# SCB_PLLs.net
KiCad netlist of a schematic drawn in Altium Designer
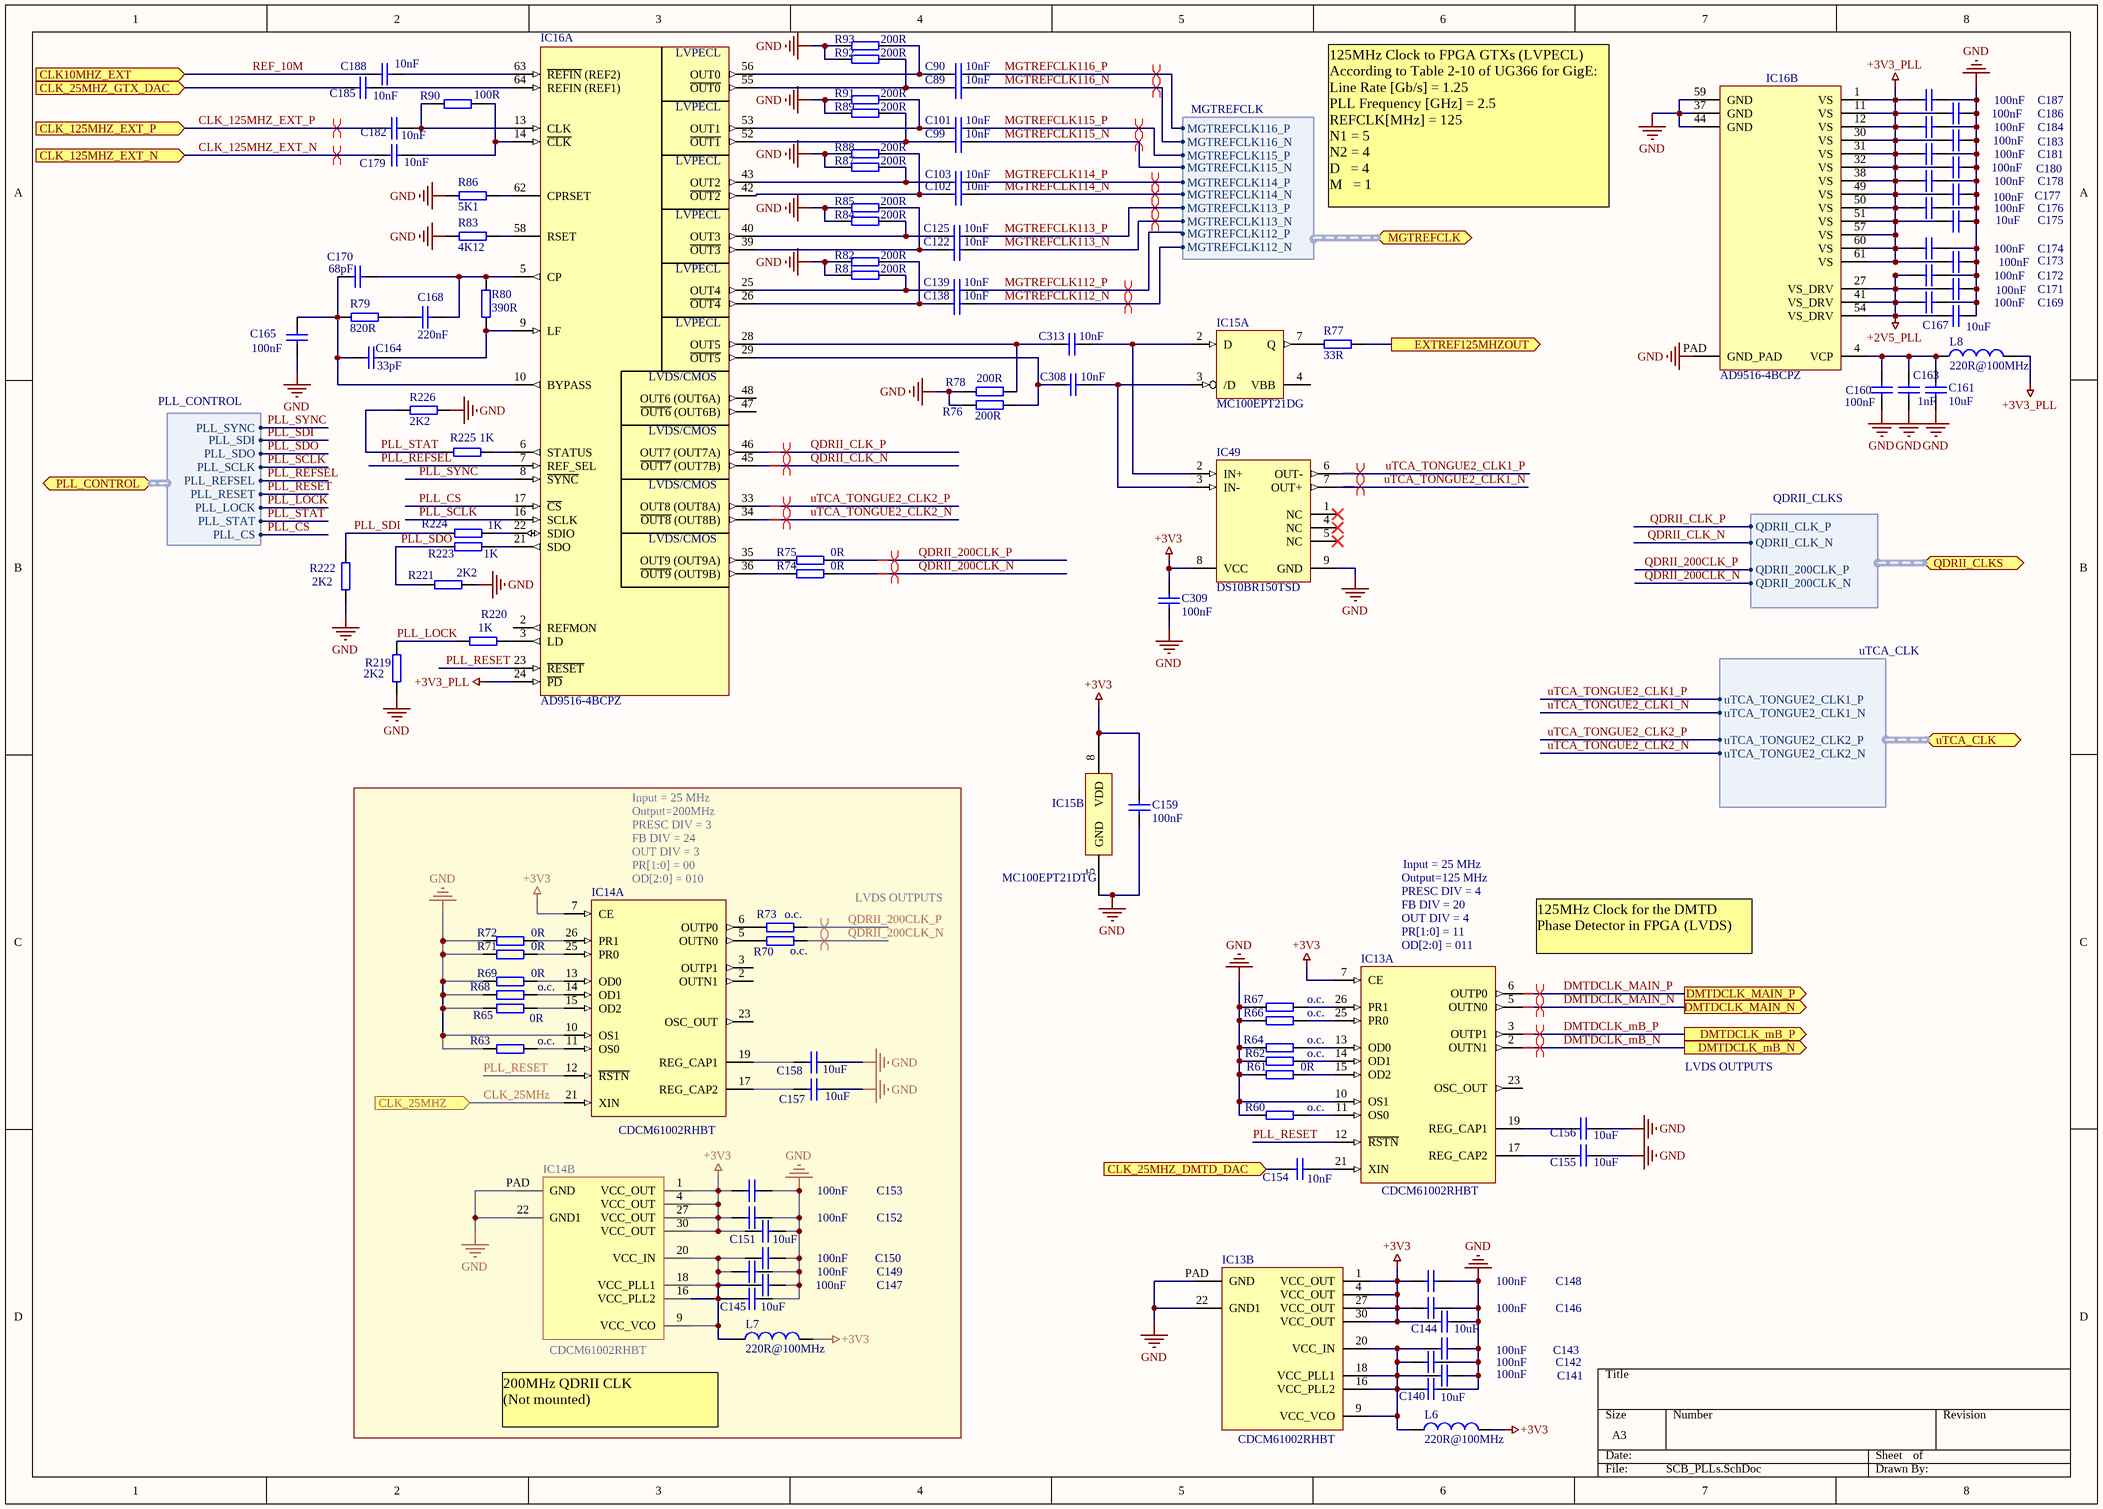
[diagram p0: SCB_PLLs.SchDoc]

(export (version "E")
  (design (tool "Eeschema 10.0.6"))
  (components
    (comp (ref "C89")
      (value "10nF")
      (footprint "CC1005-0402")
      (description "Capacitor")
      (fields
        (field (name "TOLERANCE") "±10%")
        (field (name "VOLTAGE") "25V")
        (field (name "PUBLISHER") "Altium Limited")
      )
      (libsource (lib "wr_switch") (part "Cap"))
    )
    (comp (ref "C90")
      (value "10nF")
      (footprint "CC1005-0402")
      (description "Capacitor")
      (fields
        (field (name "TOLERANCE") "±10%")
        (field (name "VOLTAGE") "25V")
        (field (name "PUBLISHER") "Altium Limited")
      )
      (libsource (lib "wr_switch") (part "Cap"))
    )
    (comp (ref "C99")
      (value "10nF")
      (footprint "CC1005-0402")
      (description "Capacitor")
      (fields
        (field (name "TOLERANCE") "±10%")
        (field (name "VOLTAGE") "25V")
        (field (name "PUBLISHER") "Altium Limited")
      )
      (libsource (lib "wr_switch") (part "Cap"))
    )
    (comp (ref "C101")
      (value "10nF")
      (footprint "CC1005-0402")
      (description "Capacitor")
      (fields
        (field (name "TOLERANCE") "±10%")
        (field (name "VOLTAGE") "25V")
        (field (name "PUBLISHER") "Altium Limited")
      )
      (libsource (lib "wr_switch") (part "Cap"))
    )
    (comp (ref "C102")
      (value "10nF")
      (footprint "CC1005-0402")
      (description "Capacitor")
      (fields
        (field (name "TOLERANCE") "±10%")
        (field (name "VOLTAGE") "25V")
        (field (name "PUBLISHER") "Altium Limited")
      )
      (libsource (lib "wr_switch") (part "Cap"))
    )
    (comp (ref "C103")
      (value "10nF")
      (footprint "CC1005-0402")
      (description "Capacitor")
      (fields
        (field (name "TOLERANCE") "±10%")
        (field (name "VOLTAGE") "25V")
        (field (name "PUBLISHER") "Altium Limited")
      )
      (libsource (lib "wr_switch") (part "Cap"))
    )
    (comp (ref "C122")
      (value "10nF")
      (footprint "CC1005-0402")
      (description "Capacitor")
      (fields
        (field (name "TOLERANCE") "±10%")
        (field (name "VOLTAGE") "25V")
        (field (name "PUBLISHER") "Altium Limited")
      )
      (libsource (lib "wr_switch") (part "Cap"))
    )
    (comp (ref "C125")
      (value "10nF")
      (footprint "CC1005-0402")
      (description "Capacitor")
      (fields
        (field (name "TOLERANCE") "±10%")
        (field (name "VOLTAGE") "25V")
        (field (name "PUBLISHER") "Altium Limited")
      )
      (libsource (lib "wr_switch") (part "Cap"))
    )
    (comp (ref "C138")
      (value "10nF")
      (footprint "CC1005-0402")
      (description "Capacitor")
      (fields
        (field (name "TOLERANCE") "±10%")
        (field (name "VOLTAGE") "25V")
        (field (name "PUBLISHER") "Altium Limited")
      )
      (libsource (lib "wr_switch") (part "Cap"))
    )
    (comp (ref "C139")
      (value "10nF")
      (footprint "CC1005-0402")
      (description "Capacitor")
      (fields
        (field (name "TOLERANCE") "±10%")
        (field (name "VOLTAGE") "25V")
        (field (name "PUBLISHER") "Altium Limited")
      )
      (libsource (lib "wr_switch") (part "Cap"))
    )
    (comp (ref "C140")
      (value "10uF")
      (footprint "CC1608-0603")
      (description "Capacitor")
      (fields
        (field (name "TOLERANCE") "±20%")
        (field (name "VOLTAGE") "6.3V")
        (field (name "PUBLISHER") "Altium Limited")
      )
      (libsource (lib "wr_switch") (part "Cap"))
    )
    (comp (ref "C141")
      (value "100nF")
      (footprint "CC1005-0402")
      (description "Capacitor")
      (fields
        (field (name "TOLERANCE") "±10%")
        (field (name "VOLTAGE") "16V")
        (field (name "PUBLISHER") "Altium Limited")
      )
      (libsource (lib "wr_switch") (part "Cap"))
    )
    (comp (ref "C142")
      (value "100nF")
      (footprint "CC1005-0402")
      (description "Capacitor")
      (fields
        (field (name "TOLERANCE") "±10%")
        (field (name "VOLTAGE") "16V")
        (field (name "PUBLISHER") "Altium Limited")
      )
      (libsource (lib "wr_switch") (part "Cap"))
    )
    (comp (ref "C143")
      (value "100nF")
      (footprint "CC1005-0402")
      (description "Capacitor")
      (fields
        (field (name "TOLERANCE") "±10%")
        (field (name "VOLTAGE") "16V")
        (field (name "PUBLISHER") "Altium Limited")
      )
      (libsource (lib "wr_switch") (part "Cap"))
    )
    (comp (ref "C144")
      (value "10uF")
      (footprint "CC1608-0603")
      (description "Capacitor")
      (fields
        (field (name "TOLERANCE") "±20%")
        (field (name "VOLTAGE") "6.3V")
        (field (name "PUBLISHER") "Altium Limited")
      )
      (libsource (lib "wr_switch") (part "Cap"))
    )
    (comp (ref "C145")
      (value "10uF")
      (footprint "CC1608-0603")
      (description "Capacitor")
      (fields
        (field (name "TOLERANCE") "±20%")
        (field (name "VOLTAGE") "6.3V")
        (field (name "PUBLISHER") "Altium Limited")
      )
      (libsource (lib "wr_switch") (part "Cap"))
    )
    (comp (ref "C146")
      (value "100nF")
      (footprint "CC1005-0402")
      (description "Capacitor")
      (fields
        (field (name "TOLERANCE") "±10%")
        (field (name "VOLTAGE") "16V")
        (field (name "PUBLISHER") "Altium Limited")
      )
      (libsource (lib "wr_switch") (part "Cap"))
    )
    (comp (ref "C147")
      (value "100nF")
      (footprint "CC1005-0402")
      (description "Capacitor")
      (fields
        (field (name "TOLERANCE") "±10%")
        (field (name "VOLTAGE") "16V")
        (field (name "PUBLISHER") "Altium Limited")
      )
      (libsource (lib "wr_switch") (part "Cap"))
    )
    (comp (ref "C148")
      (value "100nF")
      (footprint "CC1005-0402")
      (description "Capacitor")
      (fields
        (field (name "TOLERANCE") "±10%")
        (field (name "VOLTAGE") "16V")
        (field (name "PUBLISHER") "Altium Limited")
      )
      (libsource (lib "wr_switch") (part "Cap"))
    )
    (comp (ref "C149")
      (value "100nF")
      (footprint "CC1005-0402")
      (description "Capacitor")
      (fields
        (field (name "TOLERANCE") "±10%")
        (field (name "VOLTAGE") "16V")
        (field (name "PUBLISHER") "Altium Limited")
      )
      (libsource (lib "wr_switch") (part "Cap"))
    )
    (comp (ref "C150")
      (value "100nF")
      (footprint "CC1005-0402")
      (description "Capacitor")
      (fields
        (field (name "TOLERANCE") "±10%")
        (field (name "VOLTAGE") "16V")
        (field (name "PUBLISHER") "Altium Limited")
      )
      (libsource (lib "wr_switch") (part "Cap"))
    )
    (comp (ref "C151")
      (value "10uF")
      (footprint "CC1608-0603")
      (description "Capacitor")
      (fields
        (field (name "TOLERANCE") "±20%")
        (field (name "VOLTAGE") "6.3V")
        (field (name "PUBLISHER") "Altium Limited")
      )
      (libsource (lib "wr_switch") (part "Cap"))
    )
    (comp (ref "C152")
      (value "100nF")
      (footprint "CC1005-0402")
      (description "Capacitor")
      (fields
        (field (name "TOLERANCE") "±10%")
        (field (name "VOLTAGE") "16V")
        (field (name "PUBLISHER") "Altium Limited")
      )
      (libsource (lib "wr_switch") (part "Cap"))
    )
    (comp (ref "C153")
      (value "100nF")
      (footprint "CC1005-0402")
      (description "Capacitor")
      (fields
        (field (name "TOLERANCE") "±10%")
        (field (name "VOLTAGE") "16V")
        (field (name "PUBLISHER") "Altium Limited")
      )
      (libsource (lib "wr_switch") (part "Cap"))
    )
    (comp (ref "C154")
      (value "10nF")
      (footprint "CC1005-0402")
      (description "Capacitor")
      (fields
        (field (name "TOLERANCE") "±10%")
        (field (name "VOLTAGE") "25V")
        (field (name "PUBLISHER") "Altium Limited")
      )
      (libsource (lib "wr_switch") (part "Cap"))
    )
    (comp (ref "C155")
      (value "10uF")
      (footprint "CC1608-0603")
      (description "Capacitor")
      (fields
        (field (name "TOLERANCE") "±20%")
        (field (name "VOLTAGE") "6.3V")
        (field (name "PUBLISHER") "Altium Limited")
      )
      (libsource (lib "wr_switch") (part "Cap"))
    )
    (comp (ref "C156")
      (value "10uF")
      (footprint "CC1608-0603")
      (description "Capacitor")
      (fields
        (field (name "TOLERANCE") "±20%")
        (field (name "VOLTAGE") "6.3V")
        (field (name "PUBLISHER") "Altium Limited")
      )
      (libsource (lib "wr_switch") (part "Cap"))
    )
    (comp (ref "C157")
      (value "10uF")
      (footprint "CC1608-0603")
      (description "Capacitor")
      (fields
        (field (name "TOLERANCE") "±20%")
        (field (name "VOLTAGE") "6.3V")
        (field (name "PUBLISHER") "Altium Limited")
      )
      (libsource (lib "wr_switch") (part "Cap"))
    )
    (comp (ref "C158")
      (value "10uF")
      (footprint "CC1608-0603")
      (description "Capacitor")
      (fields
        (field (name "TOLERANCE") "±20%")
        (field (name "VOLTAGE") "6.3V")
        (field (name "PUBLISHER") "Altium Limited")
      )
      (libsource (lib "wr_switch") (part "Cap"))
    )
    (comp (ref "C159")
      (value "100nF")
      (footprint "CC1005-0402")
      (description "Capacitor")
      (fields
        (field (name "TOLERANCE") "±10%")
        (field (name "VOLTAGE") "16V")
        (field (name "PUBLISHER") "Altium Limited")
      )
      (libsource (lib "wr_switch") (part "Cap"))
    )
    (comp (ref "C160")
      (value "100nF")
      (footprint "CC1005-0402")
      (description "Capacitor")
      (fields
        (field (name "TOLERANCE") "±10%")
        (field (name "VOLTAGE") "16V")
        (field (name "PUBLISHER") "Altium Limited")
      )
      (libsource (lib "wr_switch") (part "Cap"))
    )
    (comp (ref "C161")
      (value "10uF")
      (footprint "CC1608-0603")
      (description "Capacitor")
      (fields
        (field (name "TOLERANCE") "±20%")
        (field (name "VOLTAGE") "6.3V")
        (field (name "PUBLISHER") "Altium Limited")
      )
      (libsource (lib "wr_switch") (part "Cap"))
    )
    (comp (ref "C163")
      (value "1nF")
      (footprint "CC1005-0402")
      (description "Capacitor")
      (fields
        (field (name "TOLERANCE") "±10%")
        (field (name "VOLTAGE") "25V")
        (field (name "PUBLISHER") "Altium Limited")
      )
      (libsource (lib "wr_switch") (part "Cap"))
    )
    (comp (ref "C164")
      (value "33pF")
      (footprint "CC1608-0603")
      (description "Capacitor")
      (fields
        (field (name "TOLERANCE") "±5%")
        (field (name "VOLTAGE") "50V")
        (field (name "PUBLISHER") "Altium Limited")
      )
      (libsource (lib "wr_switch") (part "Cap"))
    )
    (comp (ref "C165")
      (value "100nF")
      (footprint "CC1608-0603")
      (description "Capacitor")
      (fields
        (field (name "TOLERANCE") "±10%")
        (field (name "VOLTAGE") "50V")
        (field (name "PUBLISHER") "Altium Limited")
      )
      (libsource (lib "wr_switch") (part "Cap"))
    )
    (comp (ref "C167")
      (value "10uF")
      (footprint "CC1608-0603")
      (description "Capacitor")
      (fields
        (field (name "TOLERANCE") "±20%")
        (field (name "VOLTAGE") "6.3V")
        (field (name "PUBLISHER") "Altium Limited")
      )
      (libsource (lib "wr_switch") (part "Cap"))
    )
    (comp (ref "C168")
      (value "220nF")
      (footprint "CC1608-0603")
      (description "Capacitor")
      (fields
        (field (name "TOLERANCE") "±10%")
        (field (name "VOLTAGE") "10V")
        (field (name "PUBLISHER") "Altium Limited")
      )
      (libsource (lib "wr_switch") (part "Cap"))
    )
    (comp (ref "C169")
      (value "100nF")
      (footprint "CC1005-0402")
      (description "Capacitor")
      (fields
        (field (name "TOLERANCE") "±10%")
        (field (name "VOLTAGE") "16V")
        (field (name "PUBLISHER") "Altium Limited")
      )
      (libsource (lib "wr_switch") (part "Cap"))
    )
    (comp (ref "C170")
      (value "68pF")
      (footprint "CC1608-0603")
      (description "Capacitor")
      (fields
        (field (name "TOLERANCE") "±5%")
        (field (name "VOLTAGE") "50V")
        (field (name "PUBLISHER") "Altium Limited")
      )
      (libsource (lib "wr_switch") (part "Cap"))
    )
    (comp (ref "C171")
      (value "100nF")
      (footprint "CC1005-0402")
      (description "Capacitor")
      (fields
        (field (name "TOLERANCE") "±10%")
        (field (name "VOLTAGE") "16V")
        (field (name "PUBLISHER") "Altium Limited")
      )
      (libsource (lib "wr_switch") (part "Cap"))
    )
    (comp (ref "C172")
      (value "100nF")
      (footprint "CC1005-0402")
      (description "Capacitor")
      (fields
        (field (name "TOLERANCE") "±10%")
        (field (name "VOLTAGE") "16V")
        (field (name "PUBLISHER") "Altium Limited")
      )
      (libsource (lib "wr_switch") (part "Cap"))
    )
    (comp (ref "C173")
      (value "100nF")
      (footprint "CC1005-0402")
      (description "Capacitor")
      (fields
        (field (name "TOLERANCE") "±10%")
        (field (name "VOLTAGE") "16V")
        (field (name "PUBLISHER") "Altium Limited")
      )
      (libsource (lib "wr_switch") (part "Cap"))
    )
    (comp (ref "C174")
      (value "100nF")
      (footprint "CC1005-0402")
      (description "Capacitor")
      (fields
        (field (name "TOLERANCE") "±10%")
        (field (name "VOLTAGE") "16V")
        (field (name "PUBLISHER") "Altium Limited")
      )
      (libsource (lib "wr_switch") (part "Cap"))
    )
    (comp (ref "C175")
      (value "10uF")
      (footprint "CC1608-0603")
      (description "Capacitor")
      (fields
        (field (name "TOLERANCE") "±20%")
        (field (name "VOLTAGE") "6.3V")
        (field (name "PUBLISHER") "Altium Limited")
      )
      (libsource (lib "wr_switch") (part "Cap"))
    )
    (comp (ref "C176")
      (value "100nF")
      (footprint "CC1005-0402")
      (description "Capacitor")
      (fields
        (field (name "TOLERANCE") "±10%")
        (field (name "VOLTAGE") "16V")
        (field (name "PUBLISHER") "Altium Limited")
      )
      (libsource (lib "wr_switch") (part "Cap"))
    )
    (comp (ref "C177")
      (value "100nF")
      (footprint "CC1005-0402")
      (description "Capacitor")
      (fields
        (field (name "TOLERANCE") "±10%")
        (field (name "VOLTAGE") "16V")
        (field (name "PUBLISHER") "Altium Limited")
      )
      (libsource (lib "wr_switch") (part "Cap"))
    )
    (comp (ref "C178")
      (value "100nF")
      (footprint "CC1005-0402")
      (description "Capacitor")
      (fields
        (field (name "TOLERANCE") "±10%")
        (field (name "VOLTAGE") "16V")
        (field (name "PUBLISHER") "Altium Limited")
      )
      (libsource (lib "wr_switch") (part "Cap"))
    )
    (comp (ref "C179")
      (value "10nF")
      (footprint "CC1005-0402")
      (description "Capacitor")
      (fields
        (field (name "TOLERANCE") "±10%")
        (field (name "VOLTAGE") "25V")
        (field (name "PUBLISHER") "Altium Limited")
      )
      (libsource (lib "wr_switch") (part "Cap"))
    )
    (comp (ref "C180")
      (value "100nF")
      (footprint "CC1005-0402")
      (description "Capacitor")
      (fields
        (field (name "TOLERANCE") "±10%")
        (field (name "VOLTAGE") "16V")
        (field (name "PUBLISHER") "Altium Limited")
      )
      (libsource (lib "wr_switch") (part "Cap"))
    )
    (comp (ref "C181")
      (value "100nF")
      (footprint "CC1005-0402")
      (description "Capacitor")
      (fields
        (field (name "TOLERANCE") "±10%")
        (field (name "VOLTAGE") "16V")
        (field (name "PUBLISHER") "Altium Limited")
      )
      (libsource (lib "wr_switch") (part "Cap"))
    )
    (comp (ref "C182")
      (value "10nF")
      (footprint "CC1005-0402")
      (description "Capacitor")
      (fields
        (field (name "TOLERANCE") "±10%")
        (field (name "VOLTAGE") "25V")
        (field (name "PUBLISHER") "Altium Limited")
      )
      (libsource (lib "wr_switch") (part "Cap"))
    )
    (comp (ref "C183")
      (value "100nF")
      (footprint "CC1005-0402")
      (description "Capacitor")
      (fields
        (field (name "TOLERANCE") "±10%")
        (field (name "VOLTAGE") "16V")
        (field (name "PUBLISHER") "Altium Limited")
      )
      (libsource (lib "wr_switch") (part "Cap"))
    )
    (comp (ref "C184")
      (value "100nF")
      (footprint "CC1005-0402")
      (description "Capacitor")
      (fields
        (field (name "TOLERANCE") "±10%")
        (field (name "VOLTAGE") "16V")
        (field (name "PUBLISHER") "Altium Limited")
      )
      (libsource (lib "wr_switch") (part "Cap"))
    )
    (comp (ref "C185")
      (value "10nF")
      (footprint "CC1005-0402")
      (description "Capacitor")
      (fields
        (field (name "TOLERANCE") "±10%")
        (field (name "VOLTAGE") "25V")
        (field (name "PUBLISHER") "Altium Limited")
      )
      (libsource (lib "wr_switch") (part "Cap"))
    )
    (comp (ref "C186")
      (value "100nF")
      (footprint "CC1005-0402")
      (description "Capacitor")
      (fields
        (field (name "TOLERANCE") "±10%")
        (field (name "VOLTAGE") "16V")
        (field (name "PUBLISHER") "Altium Limited")
      )
      (libsource (lib "wr_switch") (part "Cap"))
    )
    (comp (ref "C187")
      (value "100nF")
      (footprint "CC1005-0402")
      (description "Capacitor")
      (fields
        (field (name "TOLERANCE") "±10%")
        (field (name "VOLTAGE") "16V")
        (field (name "PUBLISHER") "Altium Limited")
      )
      (libsource (lib "wr_switch") (part "Cap"))
    )
    (comp (ref "C188")
      (value "10nF")
      (footprint "CC1005-0402")
      (description "Capacitor")
      (fields
        (field (name "TOLERANCE") "±10%")
        (field (name "VOLTAGE") "25V")
        (field (name "PUBLISHER") "Altium Limited")
      )
      (libsource (lib "wr_switch") (part "Cap"))
    )
    (comp (ref "C308")
      (value "10nF")
      (footprint "CC1005-0402")
      (description "Capacitor")
      (fields
        (field (name "TOLERANCE") "±10%")
        (field (name "VOLTAGE") "25V")
        (field (name "PUBLISHER") "Altium Limited")
      )
      (libsource (lib "wr_switch") (part "Cap"))
    )
    (comp (ref "C309")
      (value "100nF")
      (footprint "CC1005-0402")
      (description "Capacitor")
      (fields
        (field (name "TOLERANCE") "±10%")
        (field (name "VOLTAGE") "16V")
        (field (name "PUBLISHER") "Altium Limited")
      )
      (libsource (lib "wr_switch") (part "Cap"))
    )
    (comp (ref "C313")
      (value "10nF")
      (footprint "CC1005-0402")
      (description "Capacitor")
      (fields
        (field (name "TOLERANCE") "±10%")
        (field (name "VOLTAGE") "25V")
        (field (name "PUBLISHER") "Altium Limited")
      )
      (libsource (lib "wr_switch") (part "Cap"))
    )
    (comp (ref "IC13")
      (value "CDCM61002RHBT")
      (footprint "QFN32_POWERPAD")
      (description "Low Jitter Clock Generator, Two Outpust, Integrated VCO")
      (fields (field (name "MANUFACTURER") "Texas Instruments"))
      (libsource (lib "wr_switch") (part "CDCM61002"))
    )
    (comp (ref "IC14")
      (value "CDCM61002RHBT")
      (footprint "QFN32_POWERPAD")
      (description "Low Jitter Clock Generator, Two Outpust, Integrated VCO")
      (fields (field (name "MANUFACTURER") "Texas Instruments"))
      (libsource (lib "wr_switch") (part "CDCM61002"))
    )
    (comp (ref "IC15")
      (value "MC100EPT21DG")
      (footprint "SOIC127P600-8AL")
      (description "ONSemi LVDS/LVPECL -> LVTTL/LVCMOS buffer")
      (libsource (lib "wr_switch") (part "MC100EPT21"))
    )
    (comp (ref "IC16")
      (value "AD9516-4BCPZ")
      (footprint "QFN50P900X900X100-64M")
      (description "PLL with clock fanout")
      (libsource (lib "wr_switch") (part "AD9516"))
    )
    (comp (ref "IC49")
      (value "DS10BR150TSD")
      (footprint "SDA08A")
      (description "1.0 Gbps LVDS Buffer/Repeater")
      (fields
        (field (name "MANUFACTURER") "National Semiconductor")
        (field (name "DIGIKEYPARTNUMBER") "DS10BR150TSDTR-ND")
        (field (name "PUBLISHER") "Altium Limited")
      )
      (libsource (lib "NSC Interface") (part "DS10BR150TSD"))
    )
    (comp (ref "L6")
      (value "220R@100MHz Ferrite Bead")
      (footprint "0603")
      (description "ferrite bead")
      (fields (field (name "IMPEDANCE") "220R@100MHz"))
      (libsource (lib "wr_switch") (part "L_FERRITE_BEAD"))
    )
    (comp (ref "L7")
      (value "220R@100MHz Ferrite Bead")
      (footprint "0603")
      (description "ferrite bead")
      (fields (field (name "IMPEDANCE") "220R@100MHz"))
      (libsource (lib "wr_switch") (part "L_FERRITE_BEAD"))
    )
    (comp (ref "L8")
      (value "220R@100MHz Ferrite Bead")
      (footprint "0603")
      (description "ferrite bead")
      (fields (field (name "IMPEDANCE") "220R@100MHz"))
      (libsource (lib "wr_switch") (part "L_FERRITE_BEAD"))
    )
    (comp (ref "R60")
      (value "o.c.")
      (footprint "0402")
      (description "SMD Resistor")
      (libsource (lib "wr_switch") (part "RES_SMD"))
    )
    (comp (ref "R61")
      (value "0R")
      (footprint "0402")
      (description "SMD Resistor")
      (fields (field (name "TOLERANCE") "Jumper"))
      (libsource (lib "wr_switch") (part "RES_SMD"))
    )
    (comp (ref "R62")
      (value "o.c.")
      (footprint "0402")
      (description "SMD Resistor")
      (libsource (lib "wr_switch") (part "RES_SMD"))
    )
    (comp (ref "R63")
      (value "o.c.")
      (footprint "0402")
      (description "SMD Resistor")
      (libsource (lib "wr_switch") (part "RES_SMD"))
    )
    (comp (ref "R64")
      (value "o.c.")
      (footprint "0402")
      (description "SMD Resistor")
      (libsource (lib "wr_switch") (part "RES_SMD"))
    )
    (comp (ref "R65")
      (value "0R")
      (footprint "0402")
      (description "SMD Resistor")
      (fields (field (name "TOLERANCE") "Jumper"))
      (libsource (lib "wr_switch") (part "RES_SMD"))
    )
    (comp (ref "R66")
      (value "o.c.")
      (footprint "0402")
      (description "SMD Resistor")
      (libsource (lib "wr_switch") (part "RES_SMD"))
    )
    (comp (ref "R67")
      (value "o.c.")
      (footprint "0402")
      (description "SMD Resistor")
      (libsource (lib "wr_switch") (part "RES_SMD"))
    )
    (comp (ref "R68")
      (value "o.c.")
      (footprint "0402")
      (description "SMD Resistor")
      (libsource (lib "wr_switch") (part "RES_SMD"))
    )
    (comp (ref "R69")
      (value "0R")
      (footprint "0402")
      (description "SMD Resistor")
      (fields (field (name "TOLERANCE") "Jumper"))
      (libsource (lib "wr_switch") (part "RES_SMD"))
    )
    (comp (ref "R70")
      (value "o.c.")
      (footprint "0402")
      (description "SMD Resistor")
      (libsource (lib "wr_switch") (part "RES_SMD"))
    )
    (comp (ref "R71")
      (value "0R")
      (footprint "0402")
      (description "SMD Resistor")
      (fields (field (name "TOLERANCE") "Jumper"))
      (libsource (lib "wr_switch") (part "RES_SMD"))
    )
    (comp (ref "R72")
      (value "0R")
      (footprint "0402")
      (description "SMD Resistor")
      (fields (field (name "TOLERANCE") "Jumper"))
      (libsource (lib "wr_switch") (part "RES_SMD"))
    )
    (comp (ref "R73")
      (value "o.c.")
      (footprint "0402")
      (description "SMD Resistor")
      (libsource (lib "wr_switch") (part "RES_SMD"))
    )
    (comp (ref "R74")
      (value "0R")
      (footprint "0402")
      (description "SMD Resistor")
      (fields (field (name "TOLERANCE") "Jumper"))
      (libsource (lib "wr_switch") (part "RES_SMD"))
    )
    (comp (ref "R75")
      (value "0R")
      (footprint "0402")
      (description "SMD Resistor")
      (fields (field (name "TOLERANCE") "Jumper"))
      (libsource (lib "wr_switch") (part "RES_SMD"))
    )
    (comp (ref "R76")
      (value "200R")
      (footprint "0402")
      (description "SMD Resistor")
      (fields (field (name "TOLERANCE") "±1%"))
      (libsource (lib "wr_switch") (part "RES_SMD"))
    )
    (comp (ref "R77")
      (value "33R")
      (footprint "0603")
      (description "SMD Resistor")
      (fields (field (name "TOLERANCE") "±1%"))
      (libsource (lib "wr_switch") (part "RES_SMD"))
    )
    (comp (ref "R78")
      (value "200R")
      (footprint "0402")
      (description "SMD Resistor")
      (fields (field (name "TOLERANCE") "±1%"))
      (libsource (lib "wr_switch") (part "RES_SMD"))
    )
    (comp (ref "R79")
      (value "820R")
      (footprint "0603")
      (description "SMD Resistor")
      (fields (field (name "TOLERANCE") "±1%"))
      (libsource (lib "wr_switch") (part "RES_SMD"))
    )
    (comp (ref "R80")
      (value "390R")
      (footprint "0603")
      (description "SMD Resistor")
      (fields (field (name "TOLERANCE") "±1%"))
      (libsource (lib "wr_switch") (part "RES_SMD"))
    )
    (comp (ref "R81")
      (value "200R")
      (footprint "0402")
      (description "SMD Resistor")
      (fields (field (name "TOLERANCE") "±1%"))
      (libsource (lib "wr_switch") (part "RES_SMD"))
    )
    (comp (ref "R82")
      (value "200R")
      (footprint "0402")
      (description "SMD Resistor")
      (fields (field (name "TOLERANCE") "±1%"))
      (libsource (lib "wr_switch") (part "RES_SMD"))
    )
    (comp (ref "R83")
      (value "4K12")
      (footprint "0402")
      (description "SMD Resistor")
      (fields (field (name "TOLERANCE") "±1%"))
      (libsource (lib "wr_switch") (part "RES_SMD"))
    )
    (comp (ref "R84")
      (value "200R")
      (footprint "0402")
      (description "SMD Resistor")
      (fields (field (name "TOLERANCE") "±1%"))
      (libsource (lib "wr_switch") (part "RES_SMD"))
    )
    (comp (ref "R85")
      (value "200R")
      (footprint "0402")
      (description "SMD Resistor")
      (fields (field (name "TOLERANCE") "±1%"))
      (libsource (lib "wr_switch") (part "RES_SMD"))
    )
    (comp (ref "R86")
      (value "5K1")
      (footprint "0402")
      (description "SMD Resistor")
      (fields (field (name "TOLERANCE") "±1%"))
      (libsource (lib "wr_switch") (part "RES_SMD"))
    )
    (comp (ref "R87")
      (value "200R")
      (footprint "0402")
      (description "SMD Resistor")
      (fields (field (name "TOLERANCE") "±1%"))
      (libsource (lib "wr_switch") (part "RES_SMD"))
    )
    (comp (ref "R88")
      (value "200R")
      (footprint "0402")
      (description "SMD Resistor")
      (fields (field (name "TOLERANCE") "±1%"))
      (libsource (lib "wr_switch") (part "RES_SMD"))
    )
    (comp (ref "R89")
      (value "200R")
      (footprint "0402")
      (description "SMD Resistor")
      (fields (field (name "TOLERANCE") "±1%"))
      (libsource (lib "wr_switch") (part "RES_SMD"))
    )
    (comp (ref "R90")
      (value "100R")
      (footprint "0402")
      (description "SMD Resistor")
      (fields (field (name "TOLERANCE") "±1%"))
      (libsource (lib "wr_switch") (part "RES_SMD"))
    )
    (comp (ref "R91")
      (value "200R")
      (footprint "0402")
      (description "SMD Resistor")
      (fields (field (name "TOLERANCE") "±1%"))
      (libsource (lib "wr_switch") (part "RES_SMD"))
    )
    (comp (ref "R92")
      (value "200R")
      (footprint "0402")
      (description "SMD Resistor")
      (fields (field (name "TOLERANCE") "±1%"))
      (libsource (lib "wr_switch") (part "RES_SMD"))
    )
    (comp (ref "R93")
      (value "200R")
      (footprint "0402")
      (description "SMD Resistor")
      (fields (field (name "TOLERANCE") "±1%"))
      (libsource (lib "wr_switch") (part "RES_SMD"))
    )
    (comp (ref "R219")
      (value "2K2")
      (footprint "0402")
      (description "SMD Resistor")
      (fields (field (name "TOLERANCE") "±1%"))
      (libsource (lib "wr_switch") (part "RES_SMD"))
    )
    (comp (ref "R220")
      (value "1K")
      (footprint "0402")
      (description "SMD Resistor")
      (fields (field (name "TOLERANCE") "±1%"))
      (libsource (lib "wr_switch") (part "RES_SMD"))
    )
    (comp (ref "R221")
      (value "2K2")
      (footprint "0402")
      (description "SMD Resistor")
      (fields (field (name "TOLERANCE") "±1%"))
      (libsource (lib "wr_switch") (part "RES_SMD"))
    )
    (comp (ref "R222")
      (value "2K2")
      (footprint "0402")
      (description "SMD Resistor")
      (fields (field (name "TOLERANCE") "±1%"))
      (libsource (lib "wr_switch") (part "RES_SMD"))
    )
    (comp (ref "R223")
      (value "1K")
      (footprint "0402")
      (description "SMD Resistor")
      (fields (field (name "TOLERANCE") "±1%"))
      (libsource (lib "wr_switch") (part "RES_SMD"))
    )
    (comp (ref "R224")
      (value "1K")
      (footprint "0402")
      (description "SMD Resistor")
      (fields (field (name "TOLERANCE") "±1%"))
      (libsource (lib "wr_switch") (part "RES_SMD"))
    )
    (comp (ref "R225")
      (value "1K")
      (footprint "0402")
      (description "SMD Resistor")
      (fields (field (name "TOLERANCE") "±1%"))
      (libsource (lib "wr_switch") (part "RES_SMD"))
    )
    (comp (ref "R226")
      (value "2K2")
      (footprint "0402")
      (description "SMD Resistor")
      (fields (field (name "TOLERANCE") "±1%"))
      (libsource (lib "wr_switch") (part "RES_SMD"))
    )
  )
  (nets
    (net (code "5") (name "+2V5_PLL") (class "Default")
      (node (ref "C167") (pin "1") (pinfunction "1_1") (pintype "passive"))
      (node (ref "C169") (pin "2") (pinfunction "2_2") (pintype "passive"))
      (node (ref "C171") (pin "2") (pinfunction "2_2") (pintype "passive"))
      (node (ref "C172") (pin "2") (pinfunction "2_2") (pintype "passive"))
      (node (ref "IC16") (pin "27") (pinfunction "VS_DRV_27") (pintype "power_in"))
      (node (ref "IC16") (pin "41") (pinfunction "VS_DRV_41") (pintype "power_in"))
      (node (ref "IC16") (pin "54") (pinfunction "VS_DRV_54") (pintype "power_in"))
    )
    (net (code "6") (name "+3V3") (class "Default")
      (node (ref "C144") (pin "1") (pinfunction "1_1") (pintype "passive"))
      (node (ref "C146") (pin "2") (pinfunction "2_2") (pintype "passive"))
      (node (ref "C148") (pin "2") (pinfunction "2_2") (pintype "passive"))
      (node (ref "C151") (pin "1") (pinfunction "1_1") (pintype "passive"))
      (node (ref "C152") (pin "2") (pinfunction "2_2") (pintype "passive"))
      (node (ref "C153") (pin "2") (pinfunction "2_2") (pintype "passive"))
      (node (ref "C159") (pin "1") (pinfunction "1_1") (pintype "passive"))
      (node (ref "C309") (pin "1") (pinfunction "1_1") (pintype "passive"))
      (node (ref "IC13") (pin "1") (pinfunction "VCC_OUT_1") (pintype "power_in"))
      (node (ref "IC13") (pin "27") (pinfunction "VCC_OUT_27") (pintype "power_in"))
      (node (ref "IC13") (pin "30") (pinfunction "VCC_OUT_30") (pintype "power_in"))
      (node (ref "IC13") (pin "4") (pinfunction "VCC_OUT_4") (pintype "power_in"))
      (node (ref "IC13") (pin "7") (pinfunction "CE_7") (pintype "input"))
      (node (ref "IC14") (pin "1") (pinfunction "VCC_OUT_1") (pintype "power_in"))
      (node (ref "IC14") (pin "27") (pinfunction "VCC_OUT_27") (pintype "power_in"))
      (node (ref "IC14") (pin "30") (pinfunction "VCC_OUT_30") (pintype "power_in"))
      (node (ref "IC14") (pin "4") (pinfunction "VCC_OUT_4") (pintype "power_in"))
      (node (ref "IC14") (pin "7") (pinfunction "CE_7") (pintype "input"))
      (node (ref "IC15") (pin "8") (pinfunction "VDD_8") (pintype "passive"))
      (node (ref "IC49") (pin "8") (pinfunction "VCC_8") (pintype "power_in"))
      (node (ref "L6") (pin "2") (pinfunction "2_2") (pintype "passive"))
      (node (ref "L7") (pin "2") (pinfunction "2_2") (pintype "passive"))
    )
    (net (code "7") (name "+3V3_PLL") (class "Default")
      (node (ref "C173") (pin "2") (pinfunction "2_2") (pintype "passive"))
      (node (ref "C174") (pin "2") (pinfunction "2_2") (pintype "passive"))
      (node (ref "C175") (pin "1") (pinfunction "1_1") (pintype "passive"))
      (node (ref "C176") (pin "2") (pinfunction "2_2") (pintype "passive"))
      (node (ref "C177") (pin "2") (pinfunction "2_2") (pintype "passive"))
      (node (ref "C178") (pin "2") (pinfunction "2_2") (pintype "passive"))
      (node (ref "C180") (pin "2") (pinfunction "2_2") (pintype "passive"))
      (node (ref "C181") (pin "2") (pinfunction "2_2") (pintype "passive"))
      (node (ref "C183") (pin "2") (pinfunction "2_2") (pintype "passive"))
      (node (ref "C184") (pin "2") (pinfunction "2_2") (pintype "passive"))
      (node (ref "C186") (pin "2") (pinfunction "2_2") (pintype "passive"))
      (node (ref "C187") (pin "2") (pinfunction "2_2") (pintype "passive"))
      (node (ref "IC16") (pin "1") (pinfunction "VS_1") (pintype "power_in"))
      (node (ref "IC16") (pin "11") (pinfunction "VS_11") (pintype "power_in"))
      (node (ref "IC16") (pin "12") (pinfunction "VS_12") (pintype "power_in"))
      (node (ref "IC16") (pin "24") (pinfunction "~{PD}_24") (pintype "input"))
      (node (ref "IC16") (pin "30") (pinfunction "VS_30") (pintype "power_in"))
      (node (ref "IC16") (pin "31") (pinfunction "VS_31") (pintype "power_in"))
      (node (ref "IC16") (pin "32") (pinfunction "VS_32") (pintype "power_in"))
      (node (ref "IC16") (pin "38") (pinfunction "VS_38") (pintype "power_in"))
      (node (ref "IC16") (pin "49") (pinfunction "VS_49") (pintype "power_in"))
      (node (ref "IC16") (pin "50") (pinfunction "VS_50") (pintype "power_in"))
      (node (ref "IC16") (pin "51") (pinfunction "VS_51") (pintype "power_in"))
      (node (ref "IC16") (pin "57") (pinfunction "VS_57") (pintype "power_in"))
      (node (ref "IC16") (pin "60") (pinfunction "VS_60") (pintype "power_in"))
      (node (ref "IC16") (pin "61") (pinfunction "VS_61") (pintype "power_in"))
      (node (ref "L8") (pin "2") (pinfunction "2_2") (pintype "passive"))
    )
    (net (code "8") (name "/CLK_25MHZ_DMTD_DAC") (class "Default")
      (node (ref "C154") (pin "2") (pinfunction "2_2") (pintype "passive"))
    )
    (net (code "9") (name "/CLK_25MHZ_GTX_DAC") (class "Default")
      (node (ref "C185") (pin "1") (pinfunction "1_1") (pintype "passive"))
    )
    (net (code "10") (name "/CLK_25MHz") (class "Default")
      (node (ref "IC14") (pin "21") (pinfunction "XIN_21") (pintype "input"))
    )
    (net (code "11") (name "/CLK_125MHZ_EXT_N") (class "Default")
      (node (ref "C179") (pin "1") (pinfunction "1_1") (pintype "passive"))
    )
    (net (code "12") (name "/CLK_125MHZ_EXT_P") (class "Default")
      (node (ref "C182") (pin "1") (pinfunction "1_1") (pintype "passive"))
    )
    (net (code "13") (name "/DMTDCLK_MAIN_N") (class "Default")
      (node (ref "IC13") (pin "5") (pinfunction "OUTN0_5") (pintype "output"))
    )
    (net (code "14") (name "/DMTDCLK_MAIN_P") (class "Default")
      (node (ref "IC13") (pin "6") (pinfunction "OUTP0_6") (pintype "output"))
    )
    (net (code "15") (name "/DMTDCLK_mB_N") (class "Default")
      (node (ref "IC13") (pin "2") (pinfunction "OUTN1_2") (pintype "output"))
    )
    (net (code "16") (name "/DMTDCLK_mB_P") (class "Default")
      (node (ref "IC13") (pin "3") (pinfunction "OUTP1_3") (pintype "output"))
    )
    (net (code "17") (name "/EXTREF125MHZOUT") (class "Default")
      (node (ref "R77") (pin "2") (pinfunction "2_2") (pintype "passive"))
    )
    (net (code "18") (name "/MGTREFCLK112_N") (class "Default")
      (node (ref "C138") (pin "1") (pinfunction "1_1") (pintype "passive"))
    )
    (net (code "19") (name "/MGTREFCLK112_P") (class "Default")
      (node (ref "C139") (pin "1") (pinfunction "1_1") (pintype "passive"))
    )
    (net (code "20") (name "/MGTREFCLK113_N") (class "Default")
      (node (ref "C122") (pin "1") (pinfunction "1_1") (pintype "passive"))
    )
    (net (code "21") (name "/MGTREFCLK113_P") (class "Default")
      (node (ref "C125") (pin "1") (pinfunction "1_1") (pintype "passive"))
    )
    (net (code "22") (name "/MGTREFCLK114_N") (class "Default")
      (node (ref "C102") (pin "1") (pinfunction "1_1") (pintype "passive"))
    )
    (net (code "23") (name "/MGTREFCLK114_P") (class "Default")
      (node (ref "C103") (pin "1") (pinfunction "1_1") (pintype "passive"))
    )
    (net (code "24") (name "/MGTREFCLK115_N") (class "Default")
      (node (ref "C99") (pin "1") (pinfunction "1_1") (pintype "passive"))
    )
    (net (code "25") (name "/MGTREFCLK115_P") (class "Default")
      (node (ref "C101") (pin "1") (pinfunction "1_1") (pintype "passive"))
    )
    (net (code "26") (name "/MGTREFCLK116_N") (class "Default")
      (node (ref "C89") (pin "1") (pinfunction "1_1") (pintype "passive"))
    )
    (net (code "27") (name "/MGTREFCLK116_P") (class "Default")
      (node (ref "C90") (pin "1") (pinfunction "1_1") (pintype "passive"))
    )
    (net (code "28") (name "/PLL_CS") (class "Default")
      (node (ref "IC16") (pin "17") (pinfunction "~{CS}_17") (pintype "input"))
    )
    (net (code "29") (name "/PLL_LOCK") (class "Default")
      (node (ref "R219") (pin "1") (pinfunction "1_1") (pintype "passive"))
      (node (ref "R220") (pin "2") (pinfunction "2_2") (pintype "passive"))
    )
    (net (code "30") (name "/PLL_REFSEL") (class "Default")
      (node (ref "IC16") (pin "7") (pinfunction "REF_SEL_7") (pintype "input"))
    )
    (net (code "31") (name "/PLL_RESET") (class "Default")
      (node (ref "IC13") (pin "12") (pinfunction "~{RSTN}_12") (pintype "input"))
      (node (ref "IC14") (pin "12") (pinfunction "~{RSTN}_12") (pintype "input"))
      (node (ref "IC16") (pin "23") (pinfunction "~{RESET}_23") (pintype "input"))
    )
    (net (code "32") (name "/PLL_SCLK") (class "Default")
      (node (ref "IC16") (pin "16") (pinfunction "SCLK_16") (pintype "input"))
    )
    (net (code "33") (name "/PLL_SDI") (class "Default")
      (node (ref "R222") (pin "1") (pinfunction "1_1") (pintype "passive"))
      (node (ref "R224") (pin "2") (pinfunction "2_2") (pintype "passive"))
    )
    (net (code "34") (name "/PLL_SDO") (class "Default")
      (node (ref "R221") (pin "1") (pinfunction "1_1") (pintype "passive"))
      (node (ref "R223") (pin "2") (pinfunction "2_2") (pintype "passive"))
    )
    (net (code "35") (name "/PLL_STAT") (class "Default")
      (node (ref "R225") (pin "2") (pinfunction "2_2") (pintype "passive"))
      (node (ref "R226") (pin "1") (pinfunction "1_1") (pintype "passive"))
    )
    (net (code "36") (name "/PLL_SYNC") (class "Default")
      (node (ref "IC16") (pin "8") (pinfunction "~{SYNC}_8") (pintype "input"))
    )
    (net (code "37") (name "/QDRII_200CLK_N") (class "Default")
      (node (ref "R70") (pin "1") (pinfunction "1_1") (pintype "passive"))
      (node (ref "R74") (pin "2") (pinfunction "2_2") (pintype "passive"))
    )
    (net (code "38") (name "/QDRII_200CLK_P") (class "Default")
      (node (ref "R73") (pin "1") (pinfunction "1_1") (pintype "passive"))
      (node (ref "R75") (pin "2") (pinfunction "2_2") (pintype "passive"))
    )
    (net (code "39") (name "/QDRII_CLK_N") (class "Default")
      (node (ref "IC16") (pin "45") (pinfunction "~{OUT7}_(OUT7B)_45") (pintype "output"))
    )
    (net (code "40") (name "/QDRII_CLK_P") (class "Default")
      (node (ref "IC16") (pin "46") (pinfunction "OUT7_(OUT7A)_46") (pintype "output"))
    )
    (net (code "41") (name "/REF_10M") (class "Default")
      (node (ref "C188") (pin "1") (pinfunction "1_1") (pintype "passive"))
    )
    (net (code "42") (name "/uTCA_TONGUE2_CLK1_N") (class "Default")
      (node (ref "IC49") (pin "7") (pinfunction "OUT+_7") (pintype "output"))
    )
    (net (code "43") (name "/uTCA_TONGUE2_CLK1_P") (class "Default")
      (node (ref "IC49") (pin "6") (pinfunction "OUT-_6") (pintype "output"))
    )
    (net (code "44") (name "/uTCA_TONGUE2_CLK2_N") (class "Default")
      (node (ref "IC16") (pin "34") (pinfunction "~{OUT8}_(OUT8B)_34") (pintype "output"))
    )
    (net (code "45") (name "/uTCA_TONGUE2_CLK2_P") (class "Default")
      (node (ref "IC16") (pin "33") (pinfunction "OUT8_(OUT8A)_33") (pintype "output"))
    )
    (net (code "50") (name "GND") (class "Default")
      (node (ref "C140") (pin "2") (pinfunction "2_2") (pintype "passive"))
      (node (ref "C141") (pin "1") (pinfunction "1_1") (pintype "passive"))
      (node (ref "C142") (pin "1") (pinfunction "1_1") (pintype "passive"))
      (node (ref "C143") (pin "1") (pinfunction "1_1") (pintype "passive"))
      (node (ref "C144") (pin "2") (pinfunction "2_2") (pintype "passive"))
      (node (ref "C145") (pin "2") (pinfunction "2_2") (pintype "passive"))
      (node (ref "C146") (pin "1") (pinfunction "1_1") (pintype "passive"))
      (node (ref "C147") (pin "1") (pinfunction "1_1") (pintype "passive"))
      (node (ref "C148") (pin "1") (pinfunction "1_1") (pintype "passive"))
      (node (ref "C149") (pin "1") (pinfunction "1_1") (pintype "passive"))
      (node (ref "C150") (pin "1") (pinfunction "1_1") (pintype "passive"))
      (node (ref "C151") (pin "2") (pinfunction "2_2") (pintype "passive"))
      (node (ref "C152") (pin "1") (pinfunction "1_1") (pintype "passive"))
      (node (ref "C153") (pin "1") (pinfunction "1_1") (pintype "passive"))
      (node (ref "C155") (pin "2") (pinfunction "2_2") (pintype "passive"))
      (node (ref "C156") (pin "2") (pinfunction "2_2") (pintype "passive"))
      (node (ref "C157") (pin "2") (pinfunction "2_2") (pintype "passive"))
      (node (ref "C158") (pin "2") (pinfunction "2_2") (pintype "passive"))
      (node (ref "C159") (pin "2") (pinfunction "2_2") (pintype "passive"))
      (node (ref "C160") (pin "2") (pinfunction "2_2") (pintype "passive"))
      (node (ref "C161") (pin "1") (pinfunction "1_1") (pintype "passive"))
      (node (ref "C163") (pin "1") (pinfunction "1_1") (pintype "passive"))
      (node (ref "C165") (pin "1") (pinfunction "1_1") (pintype "passive"))
      (node (ref "C167") (pin "2") (pinfunction "2_2") (pintype "passive"))
      (node (ref "C169") (pin "1") (pinfunction "1_1") (pintype "passive"))
      (node (ref "C171") (pin "1") (pinfunction "1_1") (pintype "passive"))
      (node (ref "C172") (pin "1") (pinfunction "1_1") (pintype "passive"))
      (node (ref "C173") (pin "1") (pinfunction "1_1") (pintype "passive"))
      (node (ref "C174") (pin "1") (pinfunction "1_1") (pintype "passive"))
      (node (ref "C175") (pin "2") (pinfunction "2_2") (pintype "passive"))
      (node (ref "C176") (pin "1") (pinfunction "1_1") (pintype "passive"))
      (node (ref "C177") (pin "1") (pinfunction "1_1") (pintype "passive"))
      (node (ref "C178") (pin "1") (pinfunction "1_1") (pintype "passive"))
      (node (ref "C180") (pin "1") (pinfunction "1_1") (pintype "passive"))
      (node (ref "C181") (pin "1") (pinfunction "1_1") (pintype "passive"))
      (node (ref "C183") (pin "1") (pinfunction "1_1") (pintype "passive"))
      (node (ref "C184") (pin "1") (pinfunction "1_1") (pintype "passive"))
      (node (ref "C186") (pin "1") (pinfunction "1_1") (pintype "passive"))
      (node (ref "C187") (pin "1") (pinfunction "1_1") (pintype "passive"))
      (node (ref "C309") (pin "2") (pinfunction "2_2") (pintype "passive"))
      (node (ref "IC13") (pin "10") (pinfunction "OS1_10") (pintype "input"))
      (node (ref "IC13") (pin "22") (pinfunction "GND1_22") (pintype "power_in"))
      (node (ref "IC13") (pin "PAD") (pinfunction "GND_PAD") (pintype "power_in"))
      (node (ref "IC14") (pin "10") (pinfunction "OS1_10") (pintype "input"))
      (node (ref "IC14") (pin "22") (pinfunction "GND1_22") (pintype "power_in"))
      (node (ref "IC14") (pin "PAD") (pinfunction "GND_PAD") (pintype "power_in"))
      (node (ref "IC15") (pin "5") (pinfunction "GND_5") (pintype "passive"))
      (node (ref "IC16") (pin "37") (pinfunction "GND_37") (pintype "power_in"))
      (node (ref "IC16") (pin "44") (pinfunction "GND_44") (pintype "power_in"))
      (node (ref "IC16") (pin "59") (pinfunction "GND_59") (pintype "power_in"))
      (node (ref "IC16") (pin "PAD") (pinfunction "GND_PAD_PAD") (pintype "power_in"))
      (node (ref "IC49") (pin "9") (pinfunction "GND_9") (pintype "power_in"))
      (node (ref "R219") (pin "2") (pinfunction "2_2") (pintype "passive"))
      (node (ref "R221") (pin "2") (pinfunction "2_2") (pintype "passive"))
      (node (ref "R222") (pin "2") (pinfunction "2_2") (pintype "passive"))
      (node (ref "R226") (pin "2") (pinfunction "2_2") (pintype "passive"))
      (node (ref "R60") (pin "2") (pinfunction "2_2") (pintype "passive"))
      (node (ref "R61") (pin "1") (pinfunction "1_1") (pintype "passive"))
      (node (ref "R62") (pin "2") (pinfunction "2_2") (pintype "passive"))
      (node (ref "R63") (pin "2") (pinfunction "2_2") (pintype "passive"))
      (node (ref "R64") (pin "2") (pinfunction "2_2") (pintype "passive"))
      (node (ref "R65") (pin "1") (pinfunction "1_1") (pintype "passive"))
      (node (ref "R66") (pin "2") (pinfunction "2_2") (pintype "passive"))
      (node (ref "R67") (pin "2") (pinfunction "2_2") (pintype "passive"))
      (node (ref "R68") (pin "2") (pinfunction "2_2") (pintype "passive"))
      (node (ref "R69") (pin "1") (pinfunction "1_1") (pintype "passive"))
      (node (ref "R71") (pin "1") (pinfunction "1_1") (pintype "passive"))
      (node (ref "R72") (pin "1") (pinfunction "1_1") (pintype "passive"))
      (node (ref "R76") (pin "2") (pinfunction "2_2") (pintype "passive"))
      (node (ref "R78") (pin "2") (pinfunction "2_2") (pintype "passive"))
      (node (ref "R81") (pin "2") (pinfunction "2_2") (pintype "passive"))
      (node (ref "R82") (pin "2") (pinfunction "2_2") (pintype "passive"))
      (node (ref "R83") (pin "1") (pinfunction "1_1") (pintype "passive"))
      (node (ref "R84") (pin "2") (pinfunction "2_2") (pintype "passive"))
      (node (ref "R85") (pin "2") (pinfunction "2_2") (pintype "passive"))
      (node (ref "R86") (pin "1") (pinfunction "1_1") (pintype "passive"))
      (node (ref "R87") (pin "2") (pinfunction "2_2") (pintype "passive"))
      (node (ref "R88") (pin "2") (pinfunction "2_2") (pintype "passive"))
      (node (ref "R89") (pin "2") (pinfunction "2_2") (pintype "passive"))
      (node (ref "R91") (pin "2") (pinfunction "2_2") (pintype "passive"))
      (node (ref "R92") (pin "2") (pinfunction "2_2") (pintype "passive"))
      (node (ref "R93") (pin "2") (pinfunction "2_2") (pintype "passive"))
    )
    (net (code "51") (name "Net-(C168-Pad1)") (class "Default")
      (node (ref "C168") (pin "1") (pinfunction "1_1") (pintype "passive"))
      (node (ref "R79") (pin "2") (pinfunction "2_2") (pintype "passive"))
    )
    (net (code "52") (name "Net-(IC13A-OD0)") (class "Default")
      (node (ref "IC13") (pin "13") (pinfunction "OD0_13") (pintype "input"))
      (node (ref "R64") (pin "1") (pinfunction "1_1") (pintype "passive"))
    )
    (net (code "53") (name "Net-(IC13A-OD1)") (class "Default")
      (node (ref "IC13") (pin "14") (pinfunction "OD1_14") (pintype "input"))
      (node (ref "R62") (pin "1") (pinfunction "1_1") (pintype "passive"))
    )
    (net (code "54") (name "Net-(IC13A-OD2)") (class "Default")
      (node (ref "IC13") (pin "15") (pinfunction "OD2_15") (pintype "input"))
      (node (ref "R61") (pin "2") (pinfunction "2_2") (pintype "passive"))
    )
    (net (code "55") (name "Net-(IC13A-OS0)") (class "Default")
      (node (ref "IC13") (pin "11") (pinfunction "OS0_11") (pintype "input"))
      (node (ref "R60") (pin "1") (pinfunction "1_1") (pintype "passive"))
    )
    (net (code "56") (name "Net-(IC13A-PR0)") (class "Default")
      (node (ref "IC13") (pin "25") (pinfunction "PR0_25") (pintype "input"))
      (node (ref "R66") (pin "1") (pinfunction "1_1") (pintype "passive"))
    )
    (net (code "57") (name "Net-(IC13A-PR1)") (class "Default")
      (node (ref "IC13") (pin "26") (pinfunction "PR1_26") (pintype "input"))
      (node (ref "R67") (pin "1") (pinfunction "1_1") (pintype "passive"))
    )
    (net (code "58") (name "Net-(IC13A-REG_CAP1)") (class "Default")
      (node (ref "C156") (pin "1") (pinfunction "1_1") (pintype "passive"))
      (node (ref "IC13") (pin "19") (pinfunction "REG_CAP1_19") (pintype "passive"))
    )
    (net (code "59") (name "Net-(IC13A-REG_CAP2)") (class "Default")
      (node (ref "C155") (pin "1") (pinfunction "1_1") (pintype "passive"))
      (node (ref "IC13") (pin "17") (pinfunction "REG_CAP2_17") (pintype "passive"))
    )
    (net (code "60") (name "Net-(IC13A-XIN)") (class "Default")
      (node (ref "C154") (pin "1") (pinfunction "1_1") (pintype "passive"))
      (node (ref "IC13") (pin "21") (pinfunction "XIN_21") (pintype "input"))
    )
    (net (code "61") (name "Net-(IC13B-VCC_IN)") (class "Default")
      (node (ref "C140") (pin "1") (pinfunction "1_1") (pintype "passive"))
      (node (ref "C141") (pin "2") (pinfunction "2_2") (pintype "passive"))
      (node (ref "C142") (pin "2") (pinfunction "2_2") (pintype "passive"))
      (node (ref "C143") (pin "2") (pinfunction "2_2") (pintype "passive"))
      (node (ref "IC13") (pin "16") (pinfunction "VCC_PLL2_16") (pintype "power_in"))
      (node (ref "IC13") (pin "18") (pinfunction "VCC_PLL1_18") (pintype "power_in"))
      (node (ref "IC13") (pin "20") (pinfunction "VCC_IN_20") (pintype "power_in"))
      (node (ref "IC13") (pin "9") (pinfunction "VCC_VCO_9") (pintype "power_in"))
      (node (ref "L6") (pin "1") (pinfunction "1_1") (pintype "passive"))
    )
    (net (code "62") (name "Net-(IC14A-OD0)") (class "Default")
      (node (ref "IC14") (pin "13") (pinfunction "OD0_13") (pintype "input"))
      (node (ref "R69") (pin "2") (pinfunction "2_2") (pintype "passive"))
    )
    (net (code "63") (name "Net-(IC14A-OD1)") (class "Default")
      (node (ref "IC14") (pin "14") (pinfunction "OD1_14") (pintype "input"))
      (node (ref "R68") (pin "1") (pinfunction "1_1") (pintype "passive"))
    )
    (net (code "64") (name "Net-(IC14A-OD2)") (class "Default")
      (node (ref "IC14") (pin "15") (pinfunction "OD2_15") (pintype "input"))
      (node (ref "R65") (pin "2") (pinfunction "2_2") (pintype "passive"))
    )
    (net (code "65") (name "Net-(IC14A-OS0)") (class "Default")
      (node (ref "IC14") (pin "11") (pinfunction "OS0_11") (pintype "input"))
      (node (ref "R63") (pin "1") (pinfunction "1_1") (pintype "passive"))
    )
    (net (code "66") (name "Net-(IC14A-OUTN0)") (class "Default")
      (node (ref "IC14") (pin "5") (pinfunction "OUTN0_5") (pintype "output"))
      (node (ref "R70") (pin "2") (pinfunction "2_2") (pintype "passive"))
    )
    (net (code "67") (name "Net-(IC14A-OUTP0)") (class "Default")
      (node (ref "IC14") (pin "6") (pinfunction "OUTP0_6") (pintype "output"))
      (node (ref "R73") (pin "2") (pinfunction "2_2") (pintype "passive"))
    )
    (net (code "68") (name "Net-(IC14A-PR0)") (class "Default")
      (node (ref "IC14") (pin "25") (pinfunction "PR0_25") (pintype "input"))
      (node (ref "R71") (pin "2") (pinfunction "2_2") (pintype "passive"))
    )
    (net (code "69") (name "Net-(IC14A-PR1)") (class "Default")
      (node (ref "IC14") (pin "26") (pinfunction "PR1_26") (pintype "input"))
      (node (ref "R72") (pin "2") (pinfunction "2_2") (pintype "passive"))
    )
    (net (code "70") (name "Net-(IC14A-REG_CAP1)") (class "Default")
      (node (ref "C158") (pin "1") (pinfunction "1_1") (pintype "passive"))
      (node (ref "IC14") (pin "19") (pinfunction "REG_CAP1_19") (pintype "passive"))
    )
    (net (code "71") (name "Net-(IC14A-REG_CAP2)") (class "Default")
      (node (ref "C157") (pin "1") (pinfunction "1_1") (pintype "passive"))
      (node (ref "IC14") (pin "17") (pinfunction "REG_CAP2_17") (pintype "passive"))
    )
    (net (code "72") (name "Net-(IC14B-VCC_IN)") (class "Default")
      (node (ref "C145") (pin "1") (pinfunction "1_1") (pintype "passive"))
      (node (ref "C147") (pin "2") (pinfunction "2_2") (pintype "passive"))
      (node (ref "C149") (pin "2") (pinfunction "2_2") (pintype "passive"))
      (node (ref "C150") (pin "2") (pinfunction "2_2") (pintype "passive"))
      (node (ref "IC14") (pin "16") (pinfunction "VCC_PLL2_16") (pintype "power_in"))
      (node (ref "IC14") (pin "18") (pinfunction "VCC_PLL1_18") (pintype "power_in"))
      (node (ref "IC14") (pin "20") (pinfunction "VCC_IN_20") (pintype "power_in"))
      (node (ref "IC14") (pin "9") (pinfunction "VCC_VCO_9") (pintype "power_in"))
      (node (ref "L7") (pin "1") (pinfunction "1_1") (pintype "passive"))
    )
    (net (code "73") (name "Net-(IC15A-D)") (class "Default")
      (node (ref "C313") (pin "1") (pinfunction "1_1") (pintype "passive"))
      (node (ref "IC15") (pin "2") (pinfunction "D_2") (pintype "input"))
      (node (ref "IC49") (pin "2") (pinfunction "IN+_2") (pintype "input"))
    )
    (net (code "74") (name "Net-(IC15A-Q)") (class "Default")
      (node (ref "IC15") (pin "7") (pinfunction "Q_7") (pintype "output"))
      (node (ref "R77") (pin "1") (pinfunction "1_1") (pintype "passive"))
    )
    (net (code "75") (name "Net-(IC15A-{slash}D)") (class "Default")
      (node (ref "C308") (pin "1") (pinfunction "1_1") (pintype "passive"))
      (node (ref "IC15") (pin "3") (pinfunction "/D_3") (pintype "input"))
      (node (ref "IC49") (pin "3") (pinfunction "IN-_3") (pintype "input"))
    )
    (net (code "76") (name "Net-(IC16A-BYPASS)") (class "Default")
      (node (ref "C164") (pin "1") (pinfunction "1_1") (pintype "passive"))
      (node (ref "C165") (pin "2") (pinfunction "2_2") (pintype "passive"))
      (node (ref "C170") (pin "1") (pinfunction "1_1") (pintype "passive"))
      (node (ref "IC16") (pin "10") (pinfunction "BYPASS_10") (pintype "output"))
      (node (ref "R79") (pin "1") (pinfunction "1_1") (pintype "passive"))
    )
    (net (code "77") (name "Net-(IC16A-CLK)") (class "Default")
      (node (ref "C182") (pin "2") (pinfunction "2_2") (pintype "passive"))
      (node (ref "IC16") (pin "13") (pinfunction "CLK_13") (pintype "input"))
      (node (ref "R90") (pin "2") (pinfunction "2_2") (pintype "passive"))
    )
    (net (code "78") (name "Net-(IC16A-CP)") (class "Default")
      (node (ref "C168") (pin "2") (pinfunction "2_2") (pintype "passive"))
      (node (ref "C170") (pin "2") (pinfunction "2_2") (pintype "passive"))
      (node (ref "IC16") (pin "5") (pinfunction "CP_5") (pintype "output"))
      (node (ref "R80") (pin "2") (pinfunction "2_2") (pintype "passive"))
    )
    (net (code "79") (name "Net-(IC16A-CPRSET)") (class "Default")
      (node (ref "IC16") (pin "62") (pinfunction "CPRSET_62") (pintype "passive"))
      (node (ref "R86") (pin "2") (pinfunction "2_2") (pintype "passive"))
    )
    (net (code "80") (name "Net-(IC16A-LD)") (class "Default")
      (node (ref "IC16") (pin "3") (pinfunction "LD_3") (pintype "output"))
      (node (ref "R220") (pin "1") (pinfunction "1_1") (pintype "passive"))
    )
    (net (code "81") (name "Net-(IC16A-LF)") (class "Default")
      (node (ref "C164") (pin "2") (pinfunction "2_2") (pintype "passive"))
      (node (ref "IC16") (pin "9") (pinfunction "LF_9") (pintype "input"))
      (node (ref "R80") (pin "1") (pinfunction "1_1") (pintype "passive"))
    )
    (net (code "82") (name "Net-(IC16A-OUT0)") (class "Default")
      (node (ref "C90") (pin "2") (pinfunction "2_2") (pintype "passive"))
      (node (ref "IC16") (pin "56") (pinfunction "OUT0_56") (pintype "output"))
      (node (ref "R93") (pin "1") (pinfunction "1_1") (pintype "passive"))
    )
    (net (code "83") (name "Net-(IC16A-OUT1)") (class "Default")
      (node (ref "C101") (pin "2") (pinfunction "2_2") (pintype "passive"))
      (node (ref "IC16") (pin "53") (pinfunction "OUT1_53") (pintype "output"))
      (node (ref "R91") (pin "1") (pinfunction "1_1") (pintype "passive"))
    )
    (net (code "84") (name "Net-(IC16A-OUT2)") (class "Default")
      (node (ref "C103") (pin "2") (pinfunction "2_2") (pintype "passive"))
      (node (ref "IC16") (pin "43") (pinfunction "OUT2_43") (pintype "output"))
      (node (ref "R87") (pin "1") (pinfunction "1_1") (pintype "passive"))
    )
    (net (code "85") (name "Net-(IC16A-OUT3)") (class "Default")
      (node (ref "C125") (pin "2") (pinfunction "2_2") (pintype "passive"))
      (node (ref "IC16") (pin "40") (pinfunction "OUT3_40") (pintype "output"))
      (node (ref "R84") (pin "1") (pinfunction "1_1") (pintype "passive"))
    )
    (net (code "86") (name "Net-(IC16A-OUT4)") (class "Default")
      (node (ref "C139") (pin "2") (pinfunction "2_2") (pintype "passive"))
      (node (ref "IC16") (pin "25") (pinfunction "OUT4_25") (pintype "output"))
      (node (ref "R81") (pin "1") (pinfunction "1_1") (pintype "passive"))
    )
    (net (code "87") (name "Net-(IC16A-OUT5)") (class "Default")
      (node (ref "C313") (pin "2") (pinfunction "2_2") (pintype "passive"))
      (node (ref "IC16") (pin "28") (pinfunction "OUT5_28") (pintype "output"))
      (node (ref "R78") (pin "1") (pinfunction "1_1") (pintype "passive"))
    )
    (net (code "88") (name "Net-(IC16A-OUT9_(OUT9A))") (class "Default")
      (node (ref "IC16") (pin "35") (pinfunction "OUT9_(OUT9A)_35") (pintype "output"))
      (node (ref "R75") (pin "1") (pinfunction "1_1") (pintype "passive"))
    )
    (net (code "89") (name "Net-(IC16A-REFIN_(REF1))") (class "Default")
      (node (ref "C185") (pin "2") (pinfunction "2_2") (pintype "passive"))
      (node (ref "IC16") (pin "64") (pinfunction "REFIN_(REF1)_64") (pintype "input"))
    )
    (net (code "90") (name "Net-(IC16A-RSET)") (class "Default")
      (node (ref "IC16") (pin "58") (pinfunction "RSET_58") (pintype "passive"))
      (node (ref "R83") (pin "2") (pinfunction "2_2") (pintype "passive"))
    )
    (net (code "91") (name "Net-(IC16A-SDIO)") (class "Default")
      (node (ref "IC16") (pin "22") (pinfunction "SDIO_22") (pintype "bidirectional"))
      (node (ref "R224") (pin "1") (pinfunction "1_1") (pintype "passive"))
    )
    (net (code "92") (name "Net-(IC16A-SDO)") (class "Default")
      (node (ref "IC16") (pin "21") (pinfunction "SDO_21") (pintype "output"))
      (node (ref "R223") (pin "1") (pinfunction "1_1") (pintype "passive"))
    )
    (net (code "93") (name "Net-(IC16A-STATUS)") (class "Default")
      (node (ref "IC16") (pin "6") (pinfunction "STATUS_6") (pintype "output"))
      (node (ref "R225") (pin "1") (pinfunction "1_1") (pintype "passive"))
    )
    (net (code "94") (name "Net-(IC16A-~{CLK})") (class "Default")
      (node (ref "C179") (pin "2") (pinfunction "2_2") (pintype "passive"))
      (node (ref "IC16") (pin "14") (pinfunction "~{CLK}_14") (pintype "input"))
      (node (ref "R90") (pin "1") (pinfunction "1_1") (pintype "passive"))
    )
    (net (code "95") (name "Net-(IC16A-~{OUT0})") (class "Default")
      (node (ref "C89") (pin "2") (pinfunction "2_2") (pintype "passive"))
      (node (ref "IC16") (pin "55") (pinfunction "~{OUT0}_55") (pintype "output"))
      (node (ref "R92") (pin "1") (pinfunction "1_1") (pintype "passive"))
    )
    (net (code "96") (name "Net-(IC16A-~{OUT1})") (class "Default")
      (node (ref "C99") (pin "2") (pinfunction "2_2") (pintype "passive"))
      (node (ref "IC16") (pin "52") (pinfunction "~{OUT1}_52") (pintype "output"))
      (node (ref "R89") (pin "1") (pinfunction "1_1") (pintype "passive"))
    )
    (net (code "97") (name "Net-(IC16A-~{OUT2})") (class "Default")
      (node (ref "C102") (pin "2") (pinfunction "2_2") (pintype "passive"))
      (node (ref "IC16") (pin "42") (pinfunction "~{OUT2}_42") (pintype "output"))
      (node (ref "R88") (pin "1") (pinfunction "1_1") (pintype "passive"))
    )
    (net (code "98") (name "Net-(IC16A-~{OUT3})") (class "Default")
      (node (ref "C122") (pin "2") (pinfunction "2_2") (pintype "passive"))
      (node (ref "IC16") (pin "39") (pinfunction "~{OUT3}_39") (pintype "output"))
      (node (ref "R85") (pin "1") (pinfunction "1_1") (pintype "passive"))
    )
    (net (code "99") (name "Net-(IC16A-~{OUT4})") (class "Default")
      (node (ref "C138") (pin "2") (pinfunction "2_2") (pintype "passive"))
      (node (ref "IC16") (pin "26") (pinfunction "~{OUT4}_26") (pintype "output"))
      (node (ref "R82") (pin "1") (pinfunction "1_1") (pintype "passive"))
    )
    (net (code "100") (name "Net-(IC16A-~{OUT5})") (class "Default")
      (node (ref "C308") (pin "2") (pinfunction "2_2") (pintype "passive"))
      (node (ref "IC16") (pin "29") (pinfunction "~{OUT5}_29") (pintype "output"))
      (node (ref "R76") (pin "1") (pinfunction "1_1") (pintype "passive"))
    )
    (net (code "101") (name "Net-(IC16A-~{OUT9}_(OUT9B))") (class "Default")
      (node (ref "IC16") (pin "36") (pinfunction "~{OUT9}_(OUT9B)_36") (pintype "output"))
      (node (ref "R74") (pin "1") (pinfunction "1_1") (pintype "passive"))
    )
    (net (code "102") (name "Net-(IC16A-~{REFIN}_(REF2))") (class "Default")
      (node (ref "C188") (pin "2") (pinfunction "2_2") (pintype "passive"))
      (node (ref "IC16") (pin "63") (pinfunction "~{REFIN}_(REF2)_63") (pintype "input"))
    )
    (net (code "103") (name "Net-(IC16B-VCP)") (class "Default")
      (node (ref "C160") (pin "1") (pinfunction "1_1") (pintype "passive"))
      (node (ref "C161") (pin "2") (pinfunction "2_2") (pintype "passive"))
      (node (ref "C163") (pin "2") (pinfunction "2_2") (pintype "passive"))
      (node (ref "IC16") (pin "4") (pinfunction "VCP_4") (pintype "power_in"))
      (node (ref "L8") (pin "1") (pinfunction "1_1") (pintype "passive"))
    )
    (net (code "104") (name "unconnected-(IC13A-OSC_OUT-Pad23)") (class "Default")
      (node (ref "IC13") (pin "23") (pinfunction "OSC_OUT_23") (pintype "output"))
    )
    (net (code "105") (name "unconnected-(IC14A-OSC_OUT-Pad23)") (class "Default")
      (node (ref "IC14") (pin "23") (pinfunction "OSC_OUT_23") (pintype "output"))
    )
    (net (code "106") (name "unconnected-(IC14A-OUTN1-Pad2)") (class "Default")
      (node (ref "IC14") (pin "2") (pinfunction "OUTN1_2") (pintype "output"))
    )
    (net (code "107") (name "unconnected-(IC14A-OUTP1-Pad3)") (class "Default")
      (node (ref "IC14") (pin "3") (pinfunction "OUTP1_3") (pintype "output"))
    )
    (net (code "108") (name "unconnected-(IC15A-VBB-Pad4)") (class "Default")
      (node (ref "IC15") (pin "4") (pinfunction "VBB_4") (pintype "passive"))
    )
    (net (code "109") (name "unconnected-(IC16A-OUT6_(OUT6A)-Pad48)") (class "Default")
      (node (ref "IC16") (pin "48") (pinfunction "OUT6_(OUT6A)_48") (pintype "output"))
    )
    (net (code "110") (name "unconnected-(IC16A-REFMON-Pad2)") (class "Default")
      (node (ref "IC16") (pin "2") (pinfunction "REFMON_2") (pintype "output"))
    )
    (net (code "111") (name "unconnected-(IC16A-~{OUT6}_(OUT6B)-Pad47)") (class "Default")
      (node (ref "IC16") (pin "47") (pinfunction "~{OUT6}_(OUT6B)_47") (pintype "output"))
    )
    (net (code "112") (name "unconnected-(IC49-NC-Pad1)") (class "Default")
      (node (ref "IC49") (pin "1") (pinfunction "NC_1") (pintype "passive+no_connect"))
    )
    (net (code "113") (name "unconnected-(IC49-NC-Pad4)") (class "Default")
      (node (ref "IC49") (pin "4") (pinfunction "NC_4") (pintype "passive+no_connect"))
    )
    (net (code "114") (name "unconnected-(IC49-NC-Pad5)") (class "Default")
      (node (ref "IC49") (pin "5") (pinfunction "NC_5") (pintype "passive+no_connect"))
    )
  )
)
